# rj45_breakout.net
KiCad netlist of a schematic drawn in Altium Designer
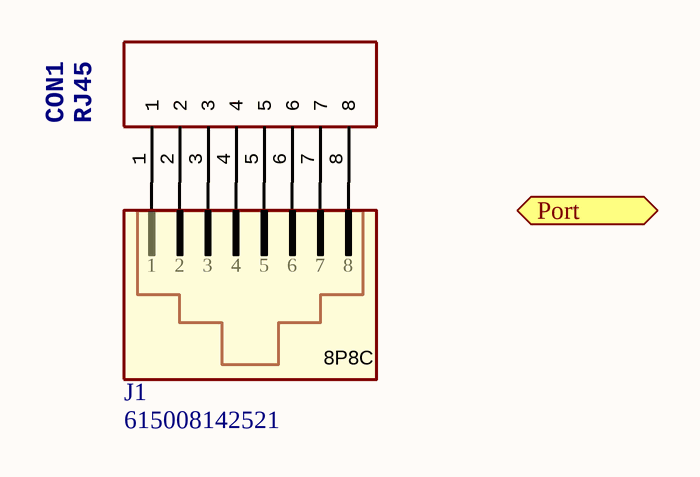
[diagram p0: rj45_breakout.SchDoc]

(export (version "E")
  (design (tool "Eeschema 10.0.6"))
  (components
    (comp (ref "CON1")
      (value "RJ45")
      (footprint "RJ45-CHASSISCONNECTOR")
      (fields (field (name "PART NUMBER") "RJ45-TOP"))
      (libsource (lib "stellalib") (part "RJ45"))
    )
    (comp (ref "J1")
      (value "615008142521")
      (footprint "615008142521")
      (fields (field (name "PUBLISHER") "Wurth Elektronik"))
      (libsource (lib "stellalib") (part "615008142521"))
    )
  )
  (nets
    (net (code "2") (name "Net-(CON1-Pad1)") (class "Default")
      (node (ref "CON1") (pin "1") (pinfunction "1_1") (pintype "passive"))
      (node (ref "J1") (pin "1") (pinfunction "1_1") (pintype "passive"))
    )
    (net (code "3") (name "Net-(CON1-Pad2)") (class "Default")
      (node (ref "CON1") (pin "2") (pinfunction "2_2") (pintype "passive"))
      (node (ref "J1") (pin "2") (pinfunction "2_2") (pintype "passive"))
    )
    (net (code "4") (name "Net-(CON1-Pad3)") (class "Default")
      (node (ref "CON1") (pin "3") (pinfunction "3_3") (pintype "passive"))
      (node (ref "J1") (pin "3") (pinfunction "3_3") (pintype "passive"))
    )
    (net (code "5") (name "Net-(CON1-Pad4)") (class "Default")
      (node (ref "CON1") (pin "4") (pinfunction "4_4") (pintype "passive"))
      (node (ref "J1") (pin "4") (pinfunction "4_4") (pintype "passive"))
    )
    (net (code "6") (name "Net-(CON1-Pad5)") (class "Default")
      (node (ref "CON1") (pin "5") (pinfunction "5_5") (pintype "passive"))
      (node (ref "J1") (pin "5") (pinfunction "5_5") (pintype "passive"))
    )
    (net (code "7") (name "Net-(CON1-Pad6)") (class "Default")
      (node (ref "CON1") (pin "6") (pinfunction "6_6") (pintype "passive"))
      (node (ref "J1") (pin "6") (pinfunction "6_6") (pintype "passive"))
    )
    (net (code "8") (name "Net-(CON1-Pad7)") (class "Default")
      (node (ref "CON1") (pin "7") (pinfunction "7_7") (pintype "passive"))
      (node (ref "J1") (pin "7") (pinfunction "7_7") (pintype "passive"))
    )
    (net (code "9") (name "Net-(CON1-Pad8)") (class "Default")
      (node (ref "CON1") (pin "8") (pinfunction "8_8") (pintype "passive"))
      (node (ref "J1") (pin "8") (pinfunction "8_8") (pintype "passive"))
    )
  )
)
